# Bluetooth.net
KiCad netlist of a schematic drawn in Altium Designer
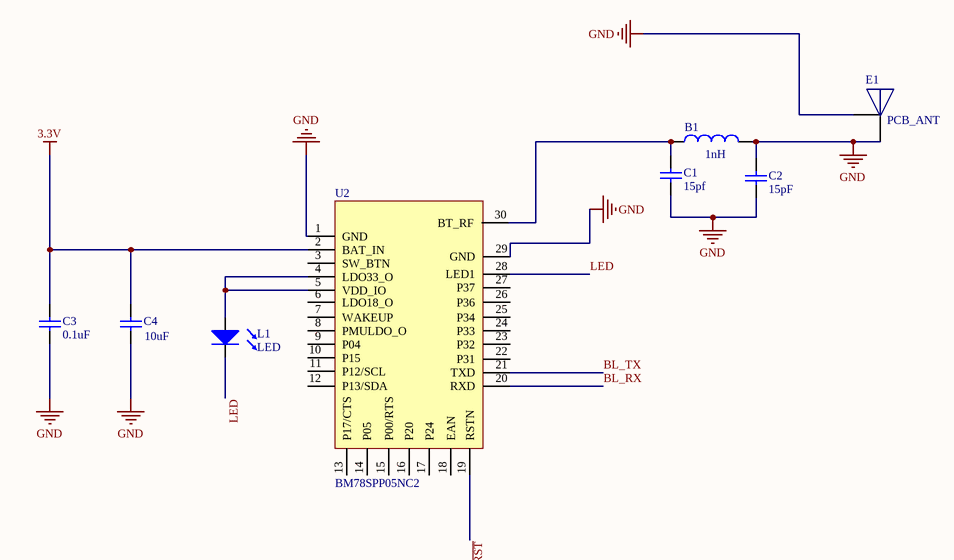
[diagram p0: Bluetooth.SchDoc]

(export (version "E")
  (design (tool "Eeschema 10.0.6"))
  (components
    (comp (ref "B1") (value "1nH") (footprint "0805") (libsource (lib "ToponLib") (part "Bead")))
    (comp (ref "C1")
      (value "15pf")
      (footprint "0603")
      (description "ceramic")
      (libsource (lib "ToponLib") (part "Cap1"))
    )
    (comp (ref "C2")
      (value "15pF")
      (footprint "0603")
      (description "ceramic")
      (libsource (lib "ToponLib") (part "Cap1"))
    )
    (comp (ref "C3")
      (value "0.1uF")
      (footprint "0603")
      (description "ceramic")
      (libsource (lib "ToponLib") (part "Cap1"))
    )
    (comp (ref "C4")
      (value "10uF")
      (footprint "0603")
      (description "ceramic")
      (libsource (lib "ToponLib") (part "Cap1"))
    )
    (comp (ref "E1")
      (value "PCB_ANT")
      (footprint "BM78SPP05NC2_ANT")
      (libsource (lib "ToponLib") (part "PCB_ANT"))
    )
    (comp (ref "L1") (value "LED") (footprint "0805") (libsource (lib "ToponLib") (part "LED")))
    (comp (ref "U2")
      (value "BM78SPP05NC2")
      (footprint "BM78SPP05NC2")
      (libsource (lib "ToponLib") (part "BM78SPP05NC2"))
    )
  )
  (nets
    (net (code "1") (name "/BL_RX") (class "Default")
      (node (ref "U2") (pin "20") (pinfunction "RXD_20") (pintype "passive"))
    )
    (net (code "2") (name "/BL_TX") (class "Default")
      (node (ref "U2") (pin "21") (pinfunction "TXD_21") (pintype "passive"))
    )
    (net (code "3") (name "/LED") (class "Default")
      (node (ref "L1") (pin "2") (pinfunction "K_2") (pintype "passive"))
      (node (ref "U2") (pin "28") (pinfunction "LED1_28") (pintype "passive"))
    )
    (net (code "4") (name "/~{RST}") (class "Default")
      (node (ref "U2") (pin "19") (pinfunction "RSTN_19") (pintype "passive"))
    )
    (net (code "5") (name "3.3V") (class "Default")
      (node (ref "C3") (pin "2") (pinfunction "2_2") (pintype "passive"))
      (node (ref "C4") (pin "2") (pinfunction "2_2") (pintype "passive"))
      (node (ref "U2") (pin "2") (pinfunction "BAT_IN_2") (pintype "passive"))
    )
    (net (code "6") (name "GND") (class "Default")
      (node (ref "B1") (pin "2") (pinfunction "2_2") (pintype "passive"))
      (node (ref "C1") (pin "1") (pinfunction "1_1") (pintype "passive"))
      (node (ref "C2") (pin "1") (pinfunction "1_1") (pintype "passive"))
      (node (ref "C2") (pin "2") (pinfunction "2_2") (pintype "passive"))
      (node (ref "C3") (pin "1") (pinfunction "1_1") (pintype "passive"))
      (node (ref "C4") (pin "1") (pinfunction "1_1") (pintype "passive"))
      (node (ref "E1") (pin "1") (pinfunction "ANT_1") (pintype "passive"))
      (node (ref "E1") (pin "2") (pinfunction "GND_2") (pintype "passive"))
      (node (ref "U2") (pin "1") (pinfunction "GND_1") (pintype "passive"))
      (node (ref "U2") (pin "29") (pinfunction "GND_29") (pintype "passive"))
    )
    (net (code "7") (name "Net-(L1-A)") (class "Default")
      (node (ref "L1") (pin "1") (pinfunction "A_1") (pintype "passive"))
      (node (ref "U2") (pin "4") (pinfunction "LDO33_O_4") (pintype "passive"))
      (node (ref "U2") (pin "5") (pinfunction "VDD_IO_5") (pintype "passive"))
    )
    (net (code "8") (name "Net-(U2-BT_RF)") (class "Default")
      (node (ref "B1") (pin "1") (pinfunction "1_1") (pintype "passive"))
      (node (ref "C1") (pin "2") (pinfunction "2_2") (pintype "passive"))
      (node (ref "U2") (pin "30") (pinfunction "BT_RF_30") (pintype "passive"))
    )
    (net (code "9") (name "unconnected-(U2-EAN-Pad18)") (class "Default")
      (node (ref "U2") (pin "18") (pinfunction "EAN_18") (pintype "passive"))
    )
    (net (code "10") (name "unconnected-(U2-LDO18_O-Pad6)") (class "Default")
      (node (ref "U2") (pin "6") (pinfunction "LDO18_O_6") (pintype "passive"))
    )
    (net (code "11") (name "unconnected-(U2-P00{slash}RTS-Pad15)") (class "Default")
      (node (ref "U2") (pin "15") (pinfunction "P00/RTS_15") (pintype "passive"))
    )
    (net (code "12") (name "unconnected-(U2-P04-Pad9)") (class "Default")
      (node (ref "U2") (pin "9") (pinfunction "P04_9") (pintype "passive"))
    )
    (net (code "13") (name "unconnected-(U2-P05-Pad14)") (class "Default")
      (node (ref "U2") (pin "14") (pinfunction "P05_14") (pintype "passive"))
    )
    (net (code "14") (name "unconnected-(U2-P12{slash}SCL-Pad11)") (class "Default")
      (node (ref "U2") (pin "11") (pinfunction "P12/SCL_11") (pintype "passive"))
    )
    (net (code "15") (name "unconnected-(U2-P13{slash}SDA-Pad12)") (class "Default")
      (node (ref "U2") (pin "12") (pinfunction "P13/SDA_12") (pintype "passive"))
    )
    (net (code "16") (name "unconnected-(U2-P15-Pad10)") (class "Default")
      (node (ref "U2") (pin "10") (pinfunction "P15_10") (pintype "passive"))
    )
    (net (code "17") (name "unconnected-(U2-P17{slash}CTS-Pad13)") (class "Default")
      (node (ref "U2") (pin "13") (pinfunction "P17/CTS_13") (pintype "passive"))
    )
    (net (code "18") (name "unconnected-(U2-P20-Pad16)") (class "Default")
      (node (ref "U2") (pin "16") (pinfunction "P20_16") (pintype "passive"))
    )
    (net (code "19") (name "unconnected-(U2-P24-Pad17)") (class "Default")
      (node (ref "U2") (pin "17") (pinfunction "P24_17") (pintype "passive"))
    )
    (net (code "20") (name "unconnected-(U2-P31-Pad22)") (class "Default")
      (node (ref "U2") (pin "22") (pinfunction "P31_22") (pintype "passive"))
    )
    (net (code "21") (name "unconnected-(U2-P32-Pad23)") (class "Default")
      (node (ref "U2") (pin "23") (pinfunction "P32_23") (pintype "passive"))
    )
    (net (code "22") (name "unconnected-(U2-P33-Pad24)") (class "Default")
      (node (ref "U2") (pin "24") (pinfunction "P33_24") (pintype "passive"))
    )
    (net (code "23") (name "unconnected-(U2-P34-Pad25)") (class "Default")
      (node (ref "U2") (pin "25") (pinfunction "P34_25") (pintype "passive"))
    )
    (net (code "24") (name "unconnected-(U2-P36-Pad26)") (class "Default")
      (node (ref "U2") (pin "26") (pinfunction "P36_26") (pintype "passive"))
    )
    (net (code "25") (name "unconnected-(U2-P37-Pad27)") (class "Default")
      (node (ref "U2") (pin "27") (pinfunction "P37_27") (pintype "passive"))
    )
    (net (code "26") (name "unconnected-(U2-PMULDO_O-Pad8)") (class "Default")
      (node (ref "U2") (pin "8") (pinfunction "PMULDO_O_8") (pintype "passive"))
    )
    (net (code "27") (name "unconnected-(U2-SW_BTN-Pad3)") (class "Default")
      (node (ref "U2") (pin "3") (pinfunction "SW_BTN_3") (pintype "passive"))
    )
    (net (code "28") (name "unconnected-(U2-WAKEUP-Pad7)") (class "Default")
      (node (ref "U2") (pin "7") (pinfunction "WAKEUP_7") (pintype "passive"))
    )
  )
)
